# Konektori_SCH.net
KiCad netlist of a schematic drawn in Altium Designer
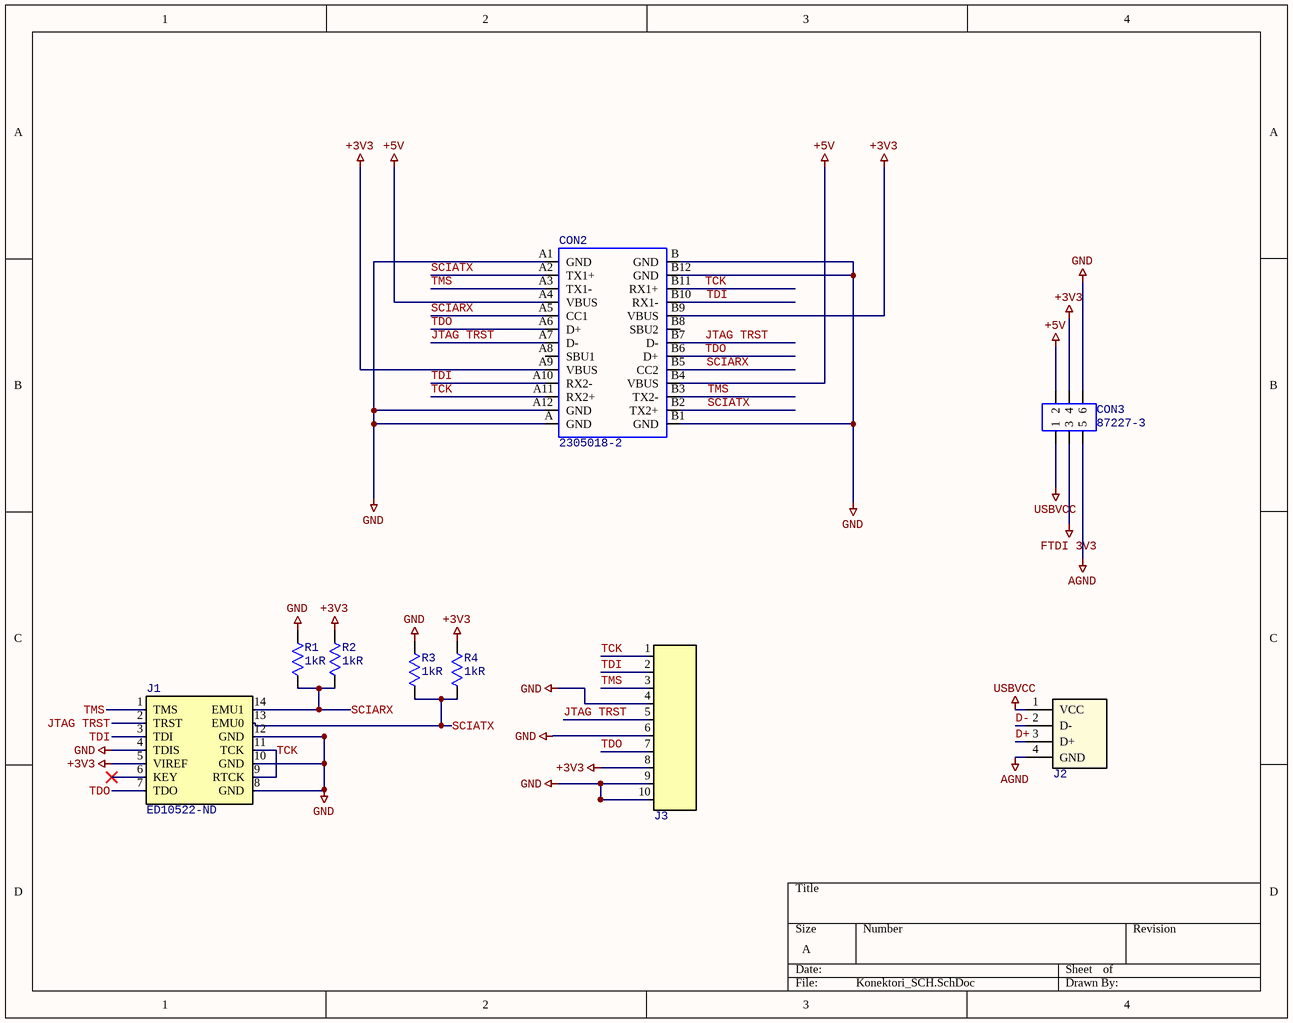
[diagram p0: Konektori_SCH.SchDoc]

(export (version "E")
  (design (tool "Eeschema 10.0.6"))
  (components
    (comp (ref "CON2")
      (value "2305018-2")
      (footprint "2305018-2")
      (description "USB C konektor")
      (libsource (lib "J_Tag") (part "2305018-2"))
    )
    (comp (ref "CON3")
      (value "87227-3")
      (footprint "87227-3")
      (description "Heder, 3x2, M")
      (libsource (lib "J_Tag") (part "87227-3"))
    )
    (comp (ref "J1")
      (value "ED10522-ND")
      (footprint "14_DIP_JTAG")
      (description "CONN HEADER VERT 14POS 2.54MM")
      (fields
        (field (name "MANUFACTURER") "On-Shore Technology")
        (field (name "MANUFACTURER PART NUMBER") "302-S141")
        (field (name "SUPPLIER PART NUMBER 1") "ED10522-ND")
      )
      (libsource (lib "Integrated_Library") (part "CONN_JTAG_Boxheader 14-pol"))
    )
    (comp (ref "J2")
      (value "USB-B1HSB6")
      (footprint "CON_RCPT_USB-B1HSB6")
      (description "CONN RCPT TYPEB 4POS R/A")
      (fields (field (name "MANUFACTURER") "On-Shore Technology"))
      (libsource (lib "Integrated_Library") (part "CON_RCTB_USB-B1HSB6"))
    )
    (comp (ref "J3")
      (value "8-215079-0")
      (footprint "CON_BTB_F_8-215079-0")
      (description "CONN FMALE-ON-BRD 10POS VERT T/H")
      (fields (field (name "MANUFACTURER") "TE Connectivity"))
      (libsource (lib "Integrated_Library") (part "CON_BTB_F_8-215079-0"))
    )
    (comp (ref "R1")
      (value "RC0603FR-071KL")
      (footprint "SMD_0603_RES")
      (description "RES SMD 1K OHM 1% 1/10W 0603")
      (fields
        (field (name "MANUFACTURER") "Yageo")
        (field (name "TOLERANCE") "1%")
        (field (name "RESISTANCE") "1kR")
      )
      (libsource (lib "Integrated_Library") (part "RES_0603_1K_1%_1/10W"))
    )
    (comp (ref "R2")
      (value "RC0603FR-071KL")
      (footprint "SMD_0603_RES")
      (description "RES SMD 1K OHM 1% 1/10W 0603")
      (fields
        (field (name "MANUFACTURER") "Yageo")
        (field (name "TOLERANCE") "1%")
        (field (name "RESISTANCE") "1kR")
      )
      (libsource (lib "Integrated_Library") (part "RES_0603_1K_1%_1/10W"))
    )
    (comp (ref "R3")
      (value "RC0603FR-071KL")
      (footprint "SMD_0603_RES")
      (description "RES SMD 1K OHM 1% 1/10W 0603")
      (fields
        (field (name "MANUFACTURER") "Yageo")
        (field (name "TOLERANCE") "1%")
        (field (name "RESISTANCE") "1kR")
      )
      (libsource (lib "Integrated_Library") (part "RES_0603_1K_1%_1/10W"))
    )
    (comp (ref "R4")
      (value "RC0603FR-071KL")
      (footprint "SMD_0603_RES")
      (description "RES SMD 1K OHM 1% 1/10W 0603")
      (fields
        (field (name "MANUFACTURER") "Yageo")
        (field (name "TOLERANCE") "1%")
        (field (name "RESISTANCE") "1kR")
      )
      (libsource (lib "Integrated_Library") (part "RES_0603_1K_1%_1/10W"))
    )
  )
  (nets
    (net (code "1") (name "+3V3") (class "Default")
      (node (ref "CON2") (pin "A9") (pinfunction "VBUS_A9") (pintype "passive"))
      (node (ref "CON2") (pin "B9") (pinfunction "VBUS_B9") (pintype "passive"))
      (node (ref "CON3") (pin "4") (pinfunction "4_4") (pintype "passive"))
      (node (ref "J1") (pin "5") (pinfunction "VIREF_5") (pintype "passive"))
      (node (ref "J3") (pin "8") (pintype "passive"))
      (node (ref "R2") (pin "2") (pinfunction "2_2") (pintype "passive"))
      (node (ref "R4") (pin "2") (pinfunction "2_2") (pintype "passive"))
    )
    (net (code "2") (name "+5V") (class "Default")
      (node (ref "CON2") (pin "A4") (pinfunction "VBUS_A4") (pintype "passive"))
      (node (ref "CON2") (pin "B4") (pinfunction "VBUS_B4") (pintype "passive"))
      (node (ref "CON3") (pin "2") (pinfunction "2_2") (pintype "passive"))
    )
    (net (code "3") (name "/D+") (class "Default")
      (node (ref "J2") (pin "3") (pinfunction "D+_3") (pintype "passive"))
    )
    (net (code "4") (name "/D-") (class "Default")
      (node (ref "J2") (pin "2") (pinfunction "D-_2") (pintype "passive"))
    )
    (net (code "5") (name "/JTAG TRST") (class "Default")
      (node (ref "CON2") (pin "A7") (pinfunction "D-_A7") (pintype "passive"))
      (node (ref "CON2") (pin "B7") (pinfunction "D-_B7") (pintype "passive"))
      (node (ref "J1") (pin "2") (pinfunction "TRST_2") (pintype "passive"))
      (node (ref "J3") (pin "5") (pintype "passive"))
    )
    (net (code "6") (name "/SCIARX") (class "Default")
      (node (ref "CON2") (pin "A5") (pinfunction "CC1_A5") (pintype "passive"))
      (node (ref "CON2") (pin "B5") (pinfunction "CC2_B5") (pintype "passive"))
      (node (ref "J1") (pin "14") (pinfunction "EMU1_14") (pintype "passive"))
      (node (ref "R1") (pin "1") (pinfunction "1_1") (pintype "passive"))
      (node (ref "R2") (pin "1") (pinfunction "1_1") (pintype "passive"))
    )
    (net (code "7") (name "/SCIATX") (class "Default")
      (node (ref "CON2") (pin "A2") (pinfunction "TX1+_A2") (pintype "passive"))
      (node (ref "CON2") (pin "B2") (pinfunction "TX2+_B2") (pintype "passive"))
      (node (ref "J1") (pin "13") (pinfunction "EMU0_13") (pintype "passive"))
      (node (ref "R3") (pin "1") (pinfunction "1_1") (pintype "passive"))
      (node (ref "R4") (pin "1") (pinfunction "1_1") (pintype "passive"))
    )
    (net (code "8") (name "/TCK") (class "Default")
      (node (ref "CON2") (pin "A11") (pinfunction "RX2+_A11") (pintype "passive"))
      (node (ref "CON2") (pin "B11") (pinfunction "RX1+_B11") (pintype "passive"))
      (node (ref "J1") (pin "11") (pinfunction "TCK_11") (pintype "passive"))
      (node (ref "J1") (pin "9") (pinfunction "RTCK_9") (pintype "passive"))
      (node (ref "J3") (pin "1") (pintype "passive"))
    )
    (net (code "9") (name "/TDI") (class "Default")
      (node (ref "CON2") (pin "A10") (pinfunction "RX2-_A10") (pintype "passive"))
      (node (ref "CON2") (pin "B10") (pinfunction "RX1-_B10") (pintype "passive"))
      (node (ref "J1") (pin "3") (pinfunction "TDI_3") (pintype "passive"))
      (node (ref "J3") (pin "2") (pintype "passive"))
    )
    (net (code "10") (name "/TDO") (class "Default")
      (node (ref "CON2") (pin "A6") (pinfunction "D+_A6") (pintype "passive"))
      (node (ref "CON2") (pin "B6") (pinfunction "D+_B6") (pintype "passive"))
      (node (ref "J1") (pin "7") (pinfunction "TDO_7") (pintype "passive"))
      (node (ref "J3") (pin "7") (pintype "passive"))
    )
    (net (code "11") (name "/TMS") (class "Default")
      (node (ref "CON2") (pin "A3") (pinfunction "TX1-_A3") (pintype "passive"))
      (node (ref "CON2") (pin "B3") (pinfunction "TX2-_B3") (pintype "passive"))
      (node (ref "J1") (pin "1") (pinfunction "TMS_1") (pintype "passive"))
      (node (ref "J3") (pin "3") (pintype "passive"))
    )
    (net (code "12") (name "AGND") (class "Default")
      (node (ref "CON3") (pin "5") (pinfunction "5_5") (pintype "passive"))
      (node (ref "J2") (pin "4") (pinfunction "GND_4") (pintype "passive"))
    )
    (net (code "13") (name "FTDI 3V3") (class "Default")
      (node (ref "CON3") (pin "3") (pinfunction "3_3") (pintype "passive"))
    )
    (net (code "14") (name "GND") (class "Default")
      (node (ref "CON2") (pin "A") (pinfunction "GND_A") (pintype "passive"))
      (node (ref "CON2") (pin "A1") (pinfunction "GND_A1") (pintype "passive"))
      (node (ref "CON2") (pin "A12") (pinfunction "GND_A12") (pintype "passive"))
      (node (ref "CON2") (pin "B") (pinfunction "GND_B") (pintype "passive"))
      (node (ref "CON2") (pin "B1") (pinfunction "GND_B1") (pintype "passive"))
      (node (ref "CON2") (pin "B12") (pinfunction "GND_B12") (pintype "passive"))
      (node (ref "CON3") (pin "6") (pinfunction "6_6") (pintype "passive"))
      (node (ref "J1") (pin "10") (pinfunction "GND_10") (pintype "passive"))
      (node (ref "J1") (pin "12") (pinfunction "GND_12") (pintype "passive"))
      (node (ref "J1") (pin "4") (pinfunction "TDIS_4") (pintype "passive"))
      (node (ref "J1") (pin "8") (pinfunction "GND_8") (pintype "passive"))
      (node (ref "J3") (pin "10") (pintype "passive"))
      (node (ref "J3") (pin "4") (pintype "passive"))
      (node (ref "J3") (pin "6") (pintype "passive"))
      (node (ref "J3") (pin "9") (pintype "passive"))
      (node (ref "R1") (pin "2") (pinfunction "2_2") (pintype "passive"))
      (node (ref "R3") (pin "2") (pinfunction "2_2") (pintype "passive"))
    )
    (net (code "15") (name "USBVCC") (class "Default")
      (node (ref "CON3") (pin "1") (pinfunction "1_1") (pintype "passive"))
      (node (ref "J2") (pin "1") (pinfunction "VCC_1") (pintype "passive"))
    )
    (net (code "16") (name "unconnected-(CON2-SBU1-PadA8)") (class "Default")
      (node (ref "CON2") (pin "A8") (pinfunction "SBU1_A8") (pintype "passive"))
    )
    (net (code "17") (name "unconnected-(CON2-SBU2-PadB8)") (class "Default")
      (node (ref "CON2") (pin "B8") (pinfunction "SBU2_B8") (pintype "passive"))
    )
    (net (code "18") (name "unconnected-(J1-KEY-Pad6)") (class "Default")
      (node (ref "J1") (pin "6") (pinfunction "KEY_6") (pintype "passive+no_connect"))
    )
  )
)
